# SCH_lora_picobaloon_2023-04-08.net
KiCad netlist of a schematic drawn in EasyEDA
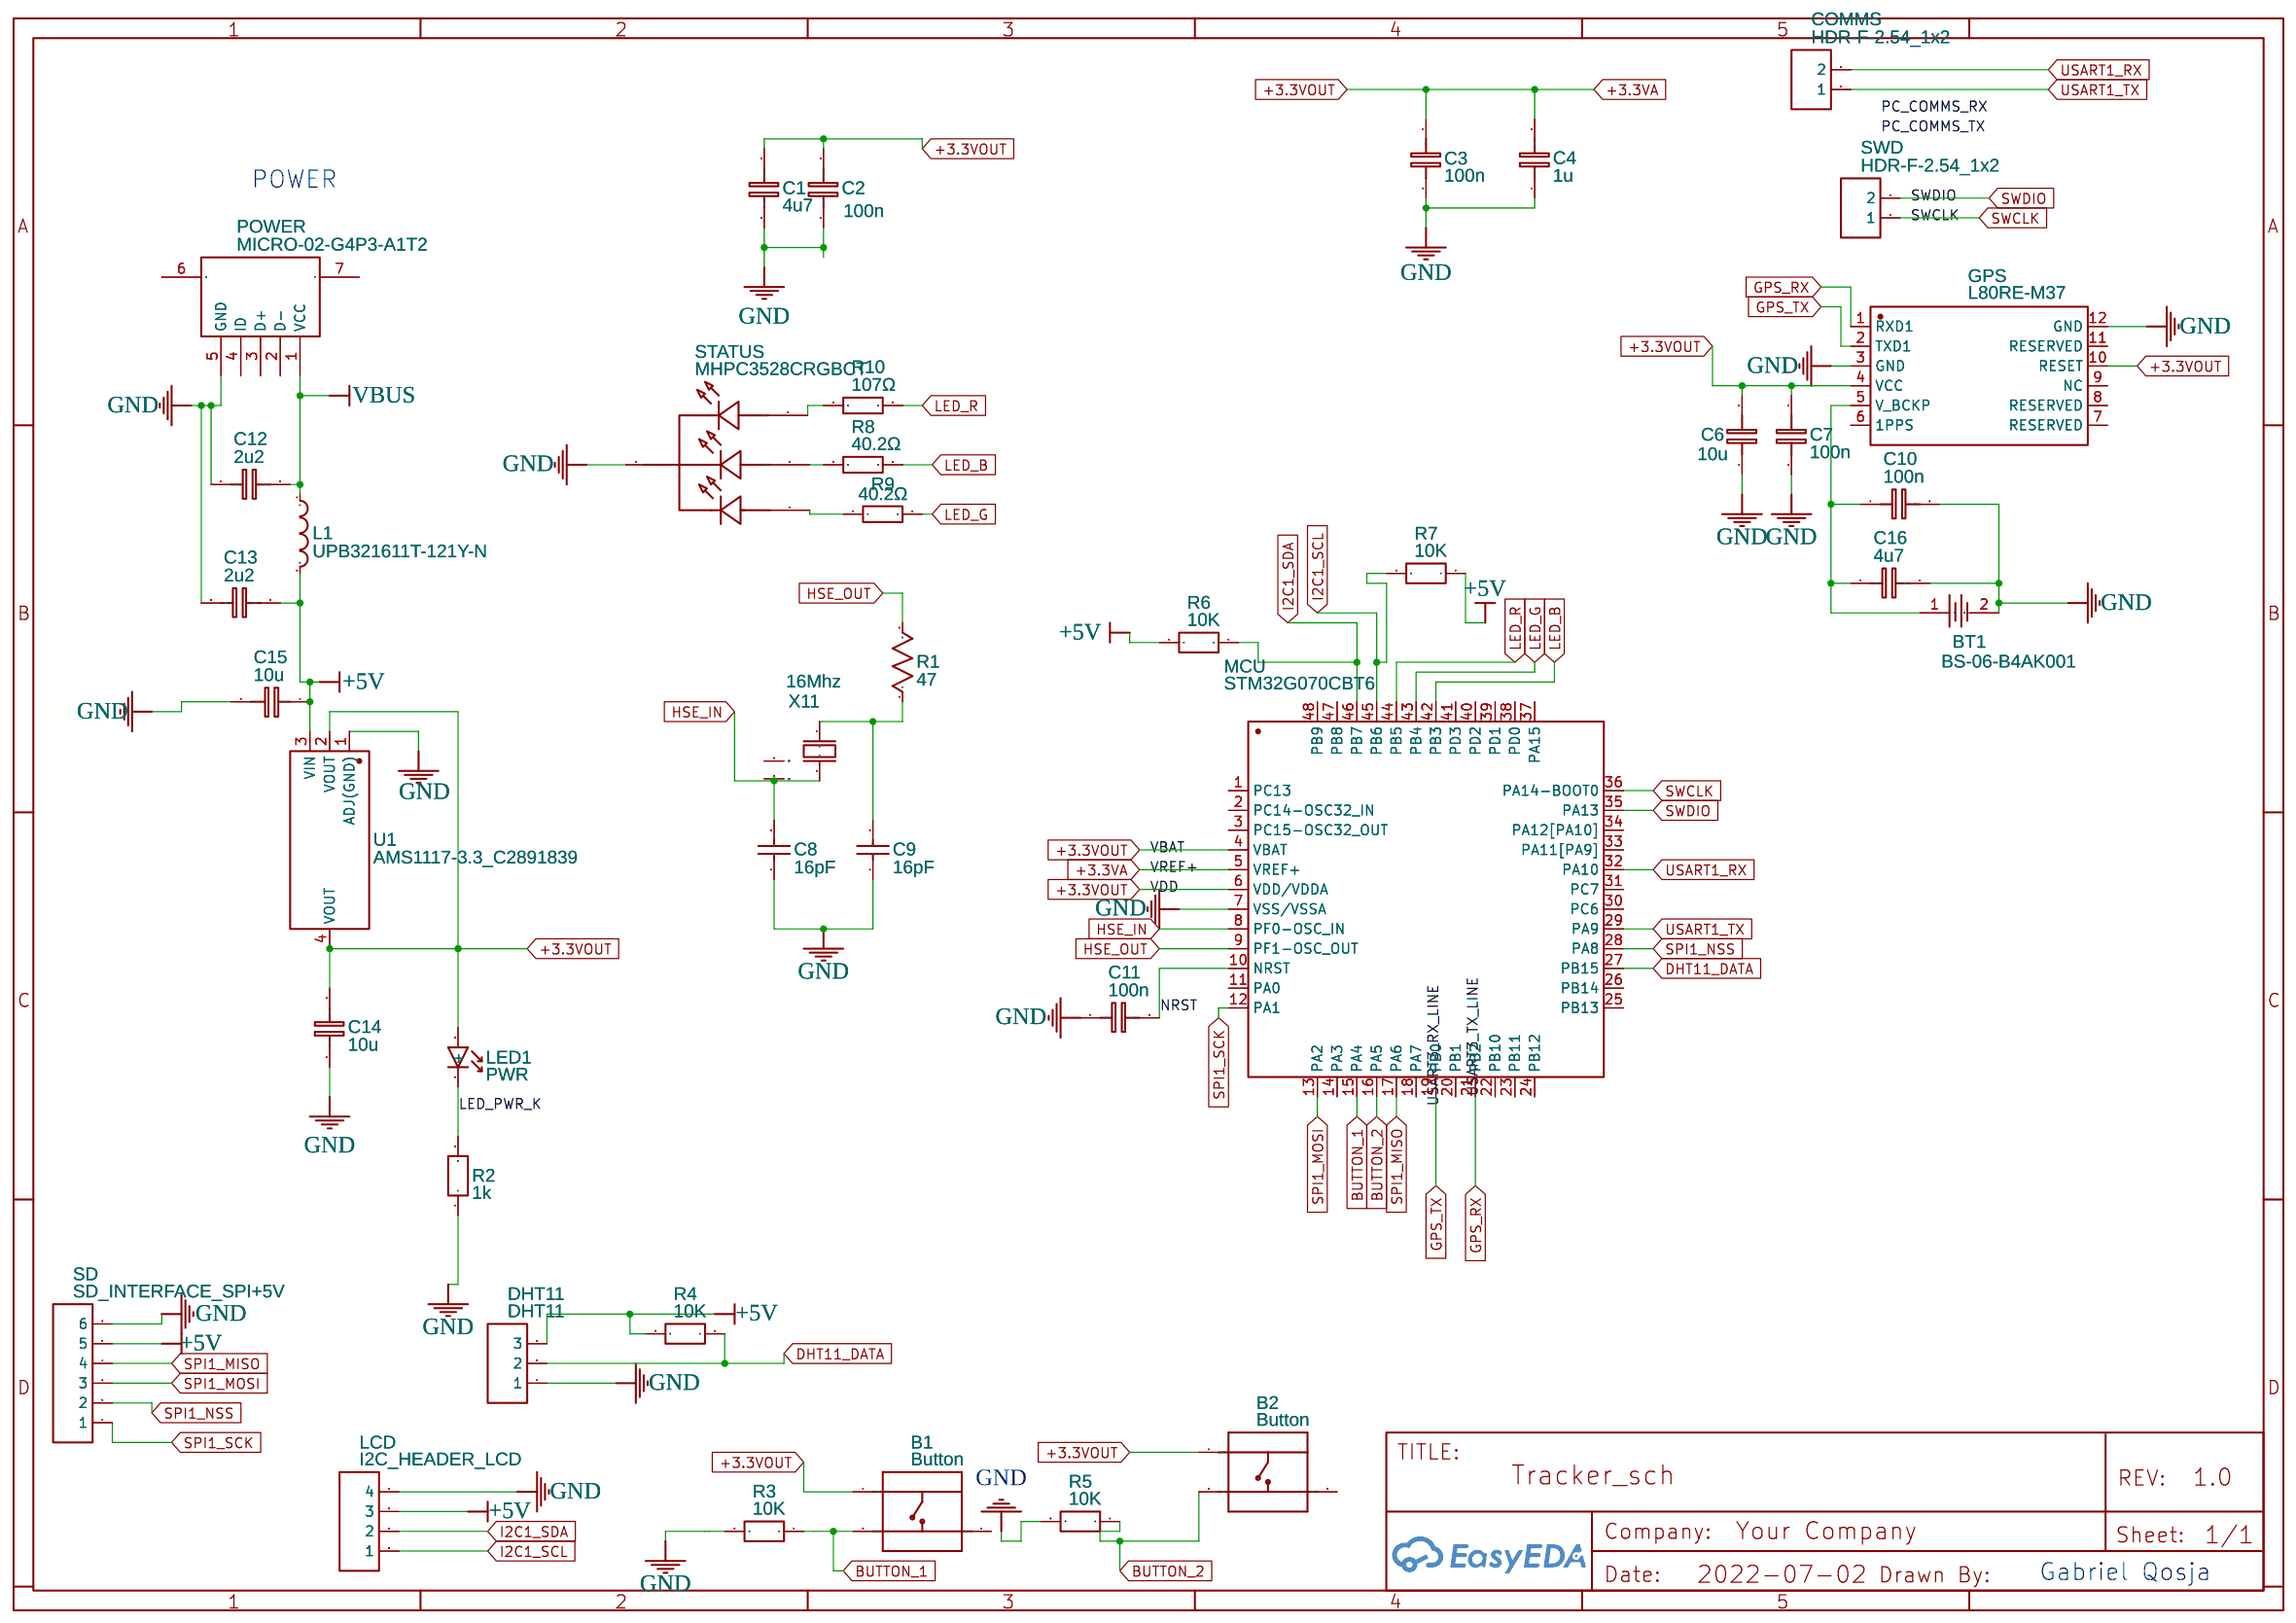
[diagram p0: schematic sheet]

(export (version "E")
  (design (tool "Eeschema 10.0.6"))
  (components
    (comp (ref "B1") (value "Button") (libsource (lib "") (part "Button")))
    (comp (ref "B2") (value "Button") (libsource (lib "") (part "Button")))
    (comp (ref "BT1")
      (value "BS-06-B4AK001")
      (fields (field (name "BOM_Supplier Part") "C964760"))
      (libsource (lib "") (part "BS-06-B4AK001"))
    )
    (comp (ref "C1")
      (value "4u7")
      (fields
        (field (name "BOM_Manufacturer Part") "CL10A475KA8NQNC")
        (field (name "BOM_Supplier Part") "C69335")
      )
      (libsource (lib "") (part "C_0603_EU_5"))
    )
    (comp (ref "C2")
      (value "100n")
      (fields
        (field (name "BOM_Manufacturer Part") "CL10B104KB8NNNC")
        (field (name "BOM_Supplier Part") "C1591")
      )
      (libsource (lib "") (part "C_0603_EU_5"))
    )
    (comp (ref "C3")
      (value "100n")
      (fields
        (field (name "BOM_Manufacturer Part") "CL10B104KB8NNNC")
        (field (name "BOM_Supplier Part") "C1591")
      )
      (libsource (lib "") (part "C_0603_EU_2"))
    )
    (comp (ref "C4")
      (value "1u")
      (fields
        (field (name "BOM_Manufacturer Part") "CL10A105KA8NNNC")
        (field (name "BOM_Supplier Part") "C5673")
      )
      (libsource (lib "") (part "C_0603_EU_2"))
    )
    (comp (ref "C6")
      (value "10u")
      (fields
        (field (name "BOM_Manufacturer Part") "CL10A106MA8NRNC")
        (field (name "BOM_Supplier Part") "C96446")
      )
      (libsource (lib "") (part "C_0603_EU_2"))
    )
    (comp (ref "C7")
      (value "100n")
      (fields
        (field (name "BOM_Manufacturer Part") "CL10B104KB8NNNC")
        (field (name "BOM_Supplier Part") "C1591")
      )
      (libsource (lib "") (part "C_0603_EU_2"))
    )
    (comp (ref "C8")
      (value "16pF")
      (fields
        (field (name "BOM_Manufacturer Part") "CL10C160JB8NNNC")
        (field (name "BOM_Supplier Part") "C170135")
      )
      (libsource (lib "") (part "0603CG160J500NT"))
    )
    (comp (ref "C9")
      (value "16pF")
      (fields
        (field (name "BOM_Manufacturer Part") "CL10C160JB8NNNC")
        (field (name "BOM_Supplier Part") "C170135")
      )
      (libsource (lib "") (part "0603CG160J500NT"))
    )
    (comp (ref "C10")
      (value "100n")
      (fields
        (field (name "BOM_Manufacturer Part") "CL10B104KB8NNNC")
        (field (name "BOM_Supplier Part") "C1591")
      )
      (libsource (lib "") (part "C_0603_EU"))
    )
    (comp (ref "C11")
      (value "100n")
      (fields
        (field (name "BOM_Manufacturer Part") "CL10B104KB8NNNC")
        (field (name "BOM_Supplier Part") "C1591")
      )
      (libsource (lib "") (part "C_0603_EU_1"))
    )
    (comp (ref "C12")
      (value "2u2")
      (fields
        (field (name "BOM_Manufacturer Part") "CL10A225KB8NNNC")
        (field (name "BOM_Supplier Part") "C913904")
      )
      (libsource (lib "") (part "C_0603_EU"))
    )
    (comp (ref "C13")
      (value "2u2")
      (fields
        (field (name "BOM_Manufacturer Part") "CL10A225KB8NNNC")
        (field (name "BOM_Supplier Part") "C913904")
      )
      (libsource (lib "") (part "C_0603_EU_1"))
    )
    (comp (ref "C14")
      (value "10u")
      (fields
        (field (name "BOM_Manufacturer Part") "CL10A106MA8NRNC")
        (field (name "BOM_Supplier Part") "C96446")
      )
      (libsource (lib "") (part "C_0603_EU_3"))
    )
    (comp (ref "C15")
      (value "10u")
      (fields
        (field (name "BOM_Manufacturer Part") "CL10A106MA8NRNC")
        (field (name "BOM_Supplier Part") "C96446")
      )
      (libsource (lib "") (part "C_0603_EU_4"))
    )
    (comp (ref "C16")
      (value "4u7")
      (fields
        (field (name "BOM_Manufacturer Part") "CL10A475KA8NQNC")
        (field (name "BOM_Supplier Part") "C69335")
      )
      (libsource (lib "") (part "C_0603_EU"))
    )
    (comp (ref "COMMS")
      (value "HDR-F-2.54_1x2")
      (fields (field (name "BOM_Supplier Part") "C49661"))
      (libsource (lib "") (part "HDR-F-2.54_1x2_1"))
    )
    (comp (ref "DHT11")
      (value "DHT11")
      (fields (field (name "BOM_Supplier Part") "C146690"))
      (libsource (lib "") (part "HDR-F-2.54_1x3"))
    )
    (comp (ref "GPS")
      (value "L80RE-M37")
      (fields (field (name "BOM_Supplier Part") "C3029061"))
      (libsource (lib "") (part "L80RE-M37"))
    )
    (comp (ref "L1")
      (value "UPB321611T-121Y-N")
      (fields (field (name "BOM_Supplier Part") "C280703"))
      (libsource (lib "") (part "UPB321611T-121Y-N"))
    )
    (comp (ref "LCD")
      (value "I2C_HEADER_LCD")
      (fields (field (name "BOM_Supplier Part") "C225501"))
      (libsource (lib "") (part "HDR-F-2.54_1x4"))
    )
    (comp (ref "LED1") (value "PWR") (libsource (lib "") (part "LED THROUGH HOLE - SIMPLE")))
    (comp (ref "MCU")
      (value "STM32G070CBT6")
      (fields (field (name "BOM_Supplier Part") "C529338"))
      (libsource (lib "") (part "STM32G070CBT6"))
    )
    (comp (ref "POWER")
      (value "MICRO-02-G4P3-A1T2")
      (fields (field (name "BOM_Supplier Part") "C2682527"))
      (libsource (lib "") (part "MICRO-02-G4P3-A1T2"))
    )
    (comp (ref "R1")
      (value "47")
      (fields
        (field (name "BOM_Manufacturer Part") "RT0603BRD0747RL")
        (field (name "BOM_Supplier Part") "C326724")
      )
      (libsource (lib "") (part "R_0603_US"))
    )
    (comp (ref "R2")
      (value "1k")
      (fields
        (field (name "BOM_Manufacturer Part") "AR03FTDX1001")
        (field (name "BOM_Supplier Part") "C304098")
      )
      (libsource (lib "") (part "R_0603_EU_1"))
    )
    (comp (ref "R3")
      (value "10K")
      (fields
        (field (name "BOM_Manufacturer Part") "RT0603BRE0710KL")
        (field (name "BOM_Supplier Part") "C136139")
      )
      (libsource (lib "") (part "R_0603_EU"))
    )
    (comp (ref "R4")
      (value "10K")
      (fields
        (field (name "BOM_Manufacturer Part") "RT0603BRE0710KL")
        (field (name "BOM_Supplier Part") "C136139")
      )
      (libsource (lib "") (part "R_0603_EU"))
    )
    (comp (ref "R5")
      (value "10K")
      (fields
        (field (name "BOM_Manufacturer Part") "RT0603BRE0710KL")
        (field (name "BOM_Supplier Part") "C136139")
      )
      (libsource (lib "") (part "R_0603_EU"))
    )
    (comp (ref "R6")
      (value "10K")
      (fields
        (field (name "BOM_Manufacturer Part") "RT0603BRE0710KL")
        (field (name "BOM_Supplier Part") "C136139")
      )
      (libsource (lib "") (part "R_0603_EU"))
    )
    (comp (ref "R7")
      (value "10K")
      (fields
        (field (name "BOM_Manufacturer Part") "RT0603BRE0710KL")
        (field (name "BOM_Supplier Part") "C136139")
      )
      (libsource (lib "") (part "R_0603_EU"))
    )
    (comp (ref "R8")
      (value "40.2Ω")
      (fields
        (field (name "BOM_Manufacturer Part") "MCR03EZPFX40R2")
        (field (name "BOM_Supplier Part") "C308259")
      )
      (libsource (lib "") (part "MCR03EZPFX40R2"))
    )
    (comp (ref "R9")
      (value "40.2Ω")
      (fields
        (field (name "BOM_Manufacturer Part") "MCR03EZPFX40R2")
        (field (name "BOM_Supplier Part") "C308259")
      )
      (libsource (lib "") (part "MCR03EZPFX40R2"))
    )
    (comp (ref "R10")
      (value "107Ω")
      (fields
        (field (name "BOM_Manufacturer Part") "RS-05K1070FT")
        (field (name "BOM_Supplier Part") "C322239")
      )
      (libsource (lib "") (part "RS-05K1070FT"))
    )
    (comp (ref "SD")
      (value "SD_INTERFACE_SPI+5V")
      (fields (field (name "BOM_Supplier Part") "C40877"))
      (libsource (lib "") (part "HDR-F-2.54_1x6"))
    )
    (comp (ref "STATUS")
      (value "MHPC3528CRGBCT")
      (fields (field (name "BOM_Supplier Part") "C2962096"))
      (libsource (lib "") (part "MHPC3528CRGBCT"))
    )
    (comp (ref "SWD")
      (value "HDR-F-2.54_1x2")
      (fields (field (name "BOM_Supplier Part") "C49661"))
      (libsource (lib "") (part "HDR-F-2.54_1x2"))
    )
    (comp (ref "U1")
      (value "AMS1117-3.3_C2891839")
      (fields
        (field (name "BOM_Manufacturer Part") "AMS1117-3.3")
        (field (name "BOM_Supplier Part") "C2891839")
      )
      (libsource (lib "") (part "AMS1117-3.3_C2891839"))
    )
    (comp (ref "X11")
      (value "16Mhz")
      (fields
        (field (name "BOM_Manufacturer Part") "3225-16.00-12-10-10/A")
        (field (name "BOM_Supplier Part") "C518161")
      )
      (libsource (lib "") (part "XTAL_4-pin_grounded"))
    )
  )
  (nets
    (net (code "1") (name "+3.3VA") (class "Default")
      (node (ref "B1") (pin "1") (pinfunction "A0_1") (pintype "unspecified"))
      (node (ref "B2") (pin "1") (pinfunction "A0_1") (pintype "unspecified"))
      (node (ref "C1") (pin "2") (pinfunction "2_2") (pintype "unspecified"))
      (node (ref "C14") (pin "2") (pinfunction "2_2") (pintype "unspecified"))
      (node (ref "C2") (pin "2") (pinfunction "2_2") (pintype "unspecified"))
      (node (ref "C3") (pin "2") (pinfunction "2_2") (pintype "unspecified"))
      (node (ref "C4") (pin "2") (pinfunction "2_2") (pintype "unspecified"))
      (node (ref "C6") (pin "2") (pinfunction "2_2") (pintype "unspecified"))
      (node (ref "C7") (pin "2") (pinfunction "2_2") (pintype "unspecified"))
      (node (ref "GPS") (pin "10") (pinfunction "RESET_10") (pintype "unspecified"))
      (node (ref "GPS") (pin "4") (pinfunction "VCC_4") (pintype "unspecified"))
      (node (ref "LED1") (pin "1") (pinfunction "+_1") (pintype "unspecified"))
      (node (ref "MCU") (pin "4") (pinfunction "VBAT_4") (pintype "unspecified"))
      (node (ref "MCU") (pin "5") (pinfunction "VREF+_5") (pintype "unspecified"))
      (node (ref "MCU") (pin "6") (pinfunction "VDD/VDDA_6") (pintype "unspecified"))
      (node (ref "U1") (pin "2") (pinfunction "VOUT_2") (pintype "unspecified"))
      (node (ref "U1") (pin "4") (pinfunction "VOUT_4") (pintype "unspecified"))
    )
    (net (code "2") (name "+5V") (class "Default")
      (node (ref "C13") (pin "2") (pinfunction "2_2") (pintype "unspecified"))
      (node (ref "C15") (pin "1") (pinfunction "1_1") (pintype "unspecified"))
      (node (ref "DHT11") (pin "3") (pinfunction "3_3") (pintype "input"))
      (node (ref "L1") (pin "2") (pinfunction "2_2") (pintype "unspecified"))
      (node (ref "LCD") (pin "3") (pinfunction "3_3") (pintype "unspecified"))
      (node (ref "R4") (pin "2") (pinfunction "2_2") (pintype "unspecified"))
      (node (ref "R6") (pin "2") (pinfunction "2_2") (pintype "unspecified"))
      (node (ref "R7") (pin "1") (pinfunction "1_1") (pintype "unspecified"))
      (node (ref "SD") (pin "5") (pinfunction "5_5") (pintype "input"))
      (node (ref "U1") (pin "3") (pinfunction "VIN_3") (pintype "unspecified"))
    )
    (net (code "3") (name "/LED_PWR_K") (class "Default")
      (node (ref "LED1") (pin "2") (pinfunction "-_2") (pintype "unspecified"))
      (node (ref "R2") (pin "2") (pinfunction "2_2") (pintype "unspecified"))
    )
    (net (code "4") (name "/NRST") (class "Default")
      (node (ref "C11") (pin "2") (pinfunction "2_2") (pintype "unspecified"))
      (node (ref "MCU") (pin "10") (pinfunction "NRST_10") (pintype "unspecified"))
    )
    (net (code "7") (name "BUTTON_1") (class "Default")
      (node (ref "B1") (pin "2") (pinfunction "B0_2") (pintype "unspecified"))
      (node (ref "MCU") (pin "15") (pinfunction "PA4_15") (pintype "unspecified"))
      (node (ref "R3") (pin "1") (pinfunction "1_1") (pintype "unspecified"))
    )
    (net (code "8") (name "BUTTON_2") (class "Default")
      (node (ref "B2") (pin "2") (pinfunction "B0_2") (pintype "unspecified"))
      (node (ref "MCU") (pin "16") (pinfunction "PA5_16") (pintype "unspecified"))
      (node (ref "R5") (pin "1") (pinfunction "1_1") (pintype "unspecified"))
    )
    (net (code "9") (name "DHT11_DATA") (class "Default")
      (node (ref "DHT11") (pin "2") (pinfunction "2_2") (pintype "input"))
      (node (ref "MCU") (pin "27") (pinfunction "PB15_27") (pintype "unspecified"))
      (node (ref "R4") (pin "1") (pinfunction "1_1") (pintype "unspecified"))
    )
    (net (code "10") (name "GND") (class "Default")
      (node (ref "BT1") (pin "2") (pinfunction "2_2") (pintype "input"))
      (node (ref "C1") (pin "1") (pinfunction "1_1") (pintype "unspecified"))
      (node (ref "C10") (pin "2") (pinfunction "2_2") (pintype "unspecified"))
      (node (ref "C11") (pin "1") (pinfunction "1_1") (pintype "unspecified"))
      (node (ref "C12") (pin "1") (pinfunction "1_1") (pintype "unspecified"))
      (node (ref "C13") (pin "1") (pinfunction "1_1") (pintype "unspecified"))
      (node (ref "C14") (pin "1") (pinfunction "1_1") (pintype "unspecified"))
      (node (ref "C15") (pin "2") (pinfunction "2_2") (pintype "unspecified"))
      (node (ref "C16") (pin "2") (pinfunction "2_2") (pintype "unspecified"))
      (node (ref "C2") (pin "1") (pinfunction "1_1") (pintype "unspecified"))
      (node (ref "C3") (pin "1") (pinfunction "1_1") (pintype "unspecified"))
      (node (ref "C4") (pin "1") (pinfunction "1_1") (pintype "unspecified"))
      (node (ref "C6") (pin "1") (pinfunction "1_1") (pintype "unspecified"))
      (node (ref "C7") (pin "1") (pinfunction "1_1") (pintype "unspecified"))
      (node (ref "C8") (pin "1") (pinfunction "1_1") (pintype "input"))
      (node (ref "C9") (pin "1") (pinfunction "1_1") (pintype "input"))
      (node (ref "DHT11") (pin "1") (pinfunction "1_1") (pintype "input"))
      (node (ref "GPS") (pin "12") (pinfunction "GND_12") (pintype "unspecified"))
      (node (ref "GPS") (pin "3") (pinfunction "GND_3") (pintype "unspecified"))
      (node (ref "LCD") (pin "4") (pinfunction "4_4") (pintype "unspecified"))
      (node (ref "MCU") (pin "7") (pinfunction "VSS/VSSA_7") (pintype "unspecified"))
      (node (ref "POWER") (pin "5") (pinfunction "GND_5") (pintype "input"))
      (node (ref "R2") (pin "1") (pinfunction "1_1") (pintype "unspecified"))
      (node (ref "R3") (pin "2") (pinfunction "2_2") (pintype "unspecified"))
      (node (ref "R5") (pin "2") (pinfunction "2_2") (pintype "unspecified"))
      (node (ref "SD") (pin "6") (pinfunction "6_6") (pintype "input"))
      (node (ref "STATUS") (pin "4") (pinfunction "-_4") (pintype "unspecified"))
      (node (ref "U1") (pin "1") (pinfunction "ADJ(GND)_1") (pintype "unspecified"))
    )
    (net (code "11") (name "GPS_RX") (class "Default")
      (node (ref "GPS") (pin "1") (pinfunction "RXD1_1") (pintype "unspecified"))
      (node (ref "MCU") (pin "21") (pinfunction "PB2_21") (pintype "unspecified"))
    )
    (net (code "12") (name "GPS_TX") (class "Default")
      (node (ref "GPS") (pin "2") (pinfunction "TXD1_2") (pintype "unspecified"))
      (node (ref "MCU") (pin "19") (pinfunction "PB0_19") (pintype "unspecified"))
    )
    (net (code "13") (name "HSE_IN") (class "Default")
      (node (ref "C8") (pin "2") (pinfunction "2_2") (pintype "input"))
      (node (ref "MCU") (pin "8") (pinfunction "PF0-OSC_IN_8") (pintype "unspecified"))
      (node (ref "X11") (pin "3") (pinfunction "out_3") (pintype "unspecified"))
    )
    (net (code "14") (name "HSE_OUT") (class "Default")
      (node (ref "MCU") (pin "9") (pinfunction "PF1-OSC_OUT_9") (pintype "unspecified"))
      (node (ref "R1") (pin "2") (pinfunction "2_2") (pintype "unspecified"))
    )
    (net (code "15") (name "I2C1_SCL") (class "Default")
      (node (ref "LCD") (pin "1") (pinfunction "1_1") (pintype "unspecified"))
      (node (ref "MCU") (pin "45") (pinfunction "PB6_45") (pintype "unspecified"))
      (node (ref "R7") (pin "2") (pinfunction "2_2") (pintype "unspecified"))
    )
    (net (code "16") (name "I2C1_SDA") (class "Default")
      (node (ref "LCD") (pin "2") (pinfunction "2_2") (pintype "unspecified"))
      (node (ref "MCU") (pin "46") (pinfunction "PB7_46") (pintype "unspecified"))
      (node (ref "R6") (pin "1") (pinfunction "1_1") (pintype "unspecified"))
    )
    (net (code "17") (name "LED_B") (class "Default")
      (node (ref "MCU") (pin "42") (pinfunction "PB3_42") (pintype "unspecified"))
      (node (ref "R8") (pin "2") (pinfunction "2_2") (pintype "unspecified"))
    )
    (net (code "18") (name "LED_G") (class "Default")
      (node (ref "MCU") (pin "43") (pinfunction "PB4_43") (pintype "unspecified"))
      (node (ref "R9") (pin "2") (pinfunction "2_2") (pintype "unspecified"))
    )
    (net (code "19") (name "LED_R") (class "Default")
      (node (ref "MCU") (pin "44") (pinfunction "PB5_44") (pintype "unspecified"))
      (node (ref "R10") (pin "2") (pinfunction "2_2") (pintype "unspecified"))
    )
    (net (code "20") (name "Net-(GPS-V_BCKP)") (class "Default")
      (node (ref "BT1") (pin "1") (pinfunction "1_1") (pintype "input"))
      (node (ref "C10") (pin "1") (pinfunction "1_1") (pintype "unspecified"))
      (node (ref "C16") (pin "1") (pinfunction "1_1") (pintype "unspecified"))
      (node (ref "GPS") (pin "5") (pinfunction "V_BCKP_5") (pintype "unspecified"))
    )
    (net (code "21") (name "Net-(R8-Pad1)") (class "Default")
      (node (ref "R8") (pin "1") (pinfunction "1_1") (pintype "unspecified"))
      (node (ref "STATUS") (pin "2") (pinfunction "+_2") (pintype "unspecified"))
    )
    (net (code "22") (name "Net-(R9-Pad1)") (class "Default")
      (node (ref "R9") (pin "1") (pinfunction "1_1") (pintype "unspecified"))
      (node (ref "STATUS") (pin "3") (pinfunction "+_3") (pintype "unspecified"))
    )
    (net (code "23") (name "Net-(R10-Pad1)") (class "Default")
      (node (ref "R10") (pin "1") (pinfunction "1_1") (pintype "unspecified"))
      (node (ref "STATUS") (pin "1") (pinfunction "+_1") (pintype "unspecified"))
    )
    (net (code "24") (name "Net-(X11-inp)") (class "Default")
      (node (ref "C9") (pin "2") (pinfunction "2_2") (pintype "input"))
      (node (ref "R1") (pin "1") (pinfunction "1_1") (pintype "unspecified"))
      (node (ref "X11") (pin "1") (pinfunction "inp_1") (pintype "unspecified"))
    )
    (net (code "25") (name "SPI1_MISO") (class "Default")
      (node (ref "MCU") (pin "17") (pinfunction "PA6_17") (pintype "unspecified"))
      (node (ref "SD") (pin "4") (pinfunction "4_4") (pintype "input"))
    )
    (net (code "26") (name "SPI1_MOSI") (class "Default")
      (node (ref "MCU") (pin "13") (pinfunction "PA2_13") (pintype "unspecified"))
      (node (ref "SD") (pin "3") (pinfunction "3_3") (pintype "input"))
    )
    (net (code "27") (name "SPI1_NSS") (class "Default")
      (node (ref "MCU") (pin "28") (pinfunction "PA8_28") (pintype "unspecified"))
      (node (ref "SD") (pin "2") (pinfunction "2_2") (pintype "input"))
    )
    (net (code "28") (name "SPI1_SCK") (class "Default")
      (node (ref "MCU") (pin "12") (pinfunction "PA1_12") (pintype "unspecified"))
      (node (ref "SD") (pin "1") (pinfunction "1_1") (pintype "input"))
    )
    (net (code "29") (name "SWCLK") (class "Default")
      (node (ref "MCU") (pin "36") (pinfunction "PA14-BOOT0_36") (pintype "unspecified"))
      (node (ref "SWD") (pin "1") (pinfunction "1_1") (pintype "input"))
    )
    (net (code "30") (name "SWDIO") (class "Default")
      (node (ref "MCU") (pin "35") (pinfunction "PA13_35") (pintype "unspecified"))
      (node (ref "SWD") (pin "2") (pinfunction "2_2") (pintype "input"))
    )
    (net (code "31") (name "USART1_RX") (class "Default")
      (node (ref "COMMS") (pin "2") (pinfunction "2_2") (pintype "input"))
      (node (ref "MCU") (pin "32") (pinfunction "PA10_32") (pintype "unspecified"))
    )
    (net (code "32") (name "USART1_TX") (class "Default")
      (node (ref "COMMS") (pin "1") (pinfunction "1_1") (pintype "input"))
      (node (ref "MCU") (pin "29") (pinfunction "PA9_29") (pintype "unspecified"))
    )
    (net (code "33") (name "VBUS") (class "Default")
      (node (ref "C12") (pin "2") (pinfunction "2_2") (pintype "unspecified"))
      (node (ref "L1") (pin "1") (pinfunction "1_1") (pintype "unspecified"))
      (node (ref "POWER") (pin "1") (pinfunction "VCC_1") (pintype "input"))
    )
    (net (code "34") (name "unconnected-(B1-B1-Pad3)") (class "Default")
      (node (ref "B1") (pin "3") (pinfunction "B1_3") (pintype "unspecified"))
    )
    (net (code "35") (name "unconnected-(B2-B1-Pad3)") (class "Default")
      (node (ref "B2") (pin "3") (pinfunction "B1_3") (pintype "unspecified"))
    )
    (net (code "36") (name "unconnected-(GPS-1PPS-Pad6)") (class "Default")
      (node (ref "GPS") (pin "6") (pinfunction "1PPS_6") (pintype "unspecified"))
    )
    (net (code "37") (name "unconnected-(GPS-NC-Pad9)") (class "Default")
      (node (ref "GPS") (pin "9") (pinfunction "NC_9") (pintype "unspecified"))
    )
    (net (code "38") (name "unconnected-(GPS-RESERVED-Pad7)") (class "Default")
      (node (ref "GPS") (pin "7") (pinfunction "RESERVED_7") (pintype "unspecified"))
    )
    (net (code "39") (name "unconnected-(GPS-RESERVED-Pad8)") (class "Default")
      (node (ref "GPS") (pin "8") (pinfunction "RESERVED_8") (pintype "unspecified"))
    )
    (net (code "40") (name "unconnected-(GPS-RESERVED-Pad11)") (class "Default")
      (node (ref "GPS") (pin "11") (pinfunction "RESERVED_11") (pintype "unspecified"))
    )
    (net (code "41") (name "unconnected-(MCU-PA0-Pad11)") (class "Default")
      (node (ref "MCU") (pin "11") (pinfunction "PA0_11") (pintype "unspecified"))
    )
    (net (code "42") (name "unconnected-(MCU-PA3-Pad14)") (class "Default")
      (node (ref "MCU") (pin "14") (pinfunction "PA3_14") (pintype "unspecified"))
    )
    (net (code "43") (name "unconnected-(MCU-PA7-Pad18)") (class "Default")
      (node (ref "MCU") (pin "18") (pinfunction "PA7_18") (pintype "unspecified"))
    )
    (net (code "44") (name "unconnected-(MCU-PA11[PA9]-Pad33)") (class "Default")
      (node (ref "MCU") (pin "33") (pinfunction "PA11[PA9]_33") (pintype "unspecified"))
    )
    (net (code "45") (name "unconnected-(MCU-PA12[PA10]-Pad34)") (class "Default")
      (node (ref "MCU") (pin "34") (pinfunction "PA12[PA10]_34") (pintype "unspecified"))
    )
    (net (code "46") (name "unconnected-(MCU-PA15-Pad37)") (class "Default")
      (node (ref "MCU") (pin "37") (pinfunction "PA15_37") (pintype "unspecified"))
    )
    (net (code "47") (name "unconnected-(MCU-PB1-Pad20)") (class "Default")
      (node (ref "MCU") (pin "20") (pinfunction "PB1_20") (pintype "unspecified"))
    )
    (net (code "48") (name "unconnected-(MCU-PB8-Pad47)") (class "Default")
      (node (ref "MCU") (pin "47") (pinfunction "PB8_47") (pintype "unspecified"))
    )
    (net (code "49") (name "unconnected-(MCU-PB9-Pad48)") (class "Default")
      (node (ref "MCU") (pin "48") (pinfunction "PB9_48") (pintype "unspecified"))
    )
    (net (code "50") (name "unconnected-(MCU-PB10-Pad22)") (class "Default")
      (node (ref "MCU") (pin "22") (pinfunction "PB10_22") (pintype "unspecified"))
    )
    (net (code "51") (name "unconnected-(MCU-PB11-Pad23)") (class "Default")
      (node (ref "MCU") (pin "23") (pinfunction "PB11_23") (pintype "unspecified"))
    )
    (net (code "52") (name "unconnected-(MCU-PB12-Pad24)") (class "Default")
      (node (ref "MCU") (pin "24") (pinfunction "PB12_24") (pintype "unspecified"))
    )
    (net (code "53") (name "unconnected-(MCU-PB13-Pad25)") (class "Default")
      (node (ref "MCU") (pin "25") (pinfunction "PB13_25") (pintype "unspecified"))
    )
    (net (code "54") (name "unconnected-(MCU-PB14-Pad26)") (class "Default")
      (node (ref "MCU") (pin "26") (pinfunction "PB14_26") (pintype "unspecified"))
    )
    (net (code "55") (name "unconnected-(MCU-PC6-Pad30)") (class "Default")
      (node (ref "MCU") (pin "30") (pinfunction "PC6_30") (pintype "unspecified"))
    )
    (net (code "56") (name "unconnected-(MCU-PC7-Pad31)") (class "Default")
      (node (ref "MCU") (pin "31") (pinfunction "PC7_31") (pintype "unspecified"))
    )
    (net (code "57") (name "unconnected-(MCU-PC13-Pad1)") (class "Default")
      (node (ref "MCU") (pin "1") (pinfunction "PC13_1") (pintype "unspecified"))
    )
    (net (code "58") (name "unconnected-(MCU-PC14-OSC32_IN-Pad2)") (class "Default")
      (node (ref "MCU") (pin "2") (pinfunction "PC14-OSC32_IN_2") (pintype "unspecified"))
    )
    (net (code "59") (name "unconnected-(MCU-PC15-OSC32_OUT-Pad3)") (class "Default")
      (node (ref "MCU") (pin "3") (pinfunction "PC15-OSC32_OUT_3") (pintype "unspecified"))
    )
    (net (code "60") (name "unconnected-(MCU-PD0-Pad38)") (class "Default")
      (node (ref "MCU") (pin "38") (pinfunction "PD0_38") (pintype "unspecified"))
    )
    (net (code "61") (name "unconnected-(MCU-PD1-Pad39)") (class "Default")
      (node (ref "MCU") (pin "39") (pinfunction "PD1_39") (pintype "unspecified"))
    )
    (net (code "62") (name "unconnected-(MCU-PD2-Pad40)") (class "Default")
      (node (ref "MCU") (pin "40") (pinfunction "PD2_40") (pintype "unspecified"))
    )
    (net (code "63") (name "unconnected-(MCU-PD3-Pad41)") (class "Default")
      (node (ref "MCU") (pin "41") (pinfunction "PD3_41") (pintype "unspecified"))
    )
    (net (code "64") (name "unconnected-(POWER-D+-Pad3)") (class "Default")
      (node (ref "POWER") (pin "3") (pinfunction "D+_3") (pintype "input"))
    )
    (net (code "65") (name "unconnected-(POWER-D--Pad2)") (class "Default")
      (node (ref "POWER") (pin "2") (pinfunction "D-_2") (pintype "input"))
    )
    (net (code "66") (name "unconnected-(POWER-ID-Pad4)") (class "Default")
      (node (ref "POWER") (pin "4") (pinfunction "ID_4") (pintype "input"))
    )
    (net (code "67") (name "unconnected-(POWER-Pad6)") (class "Default")
      (node (ref "POWER") (pin "6") (pinfunction "6_6") (pintype "input"))
    )
    (net (code "68") (name "unconnected-(POWER-Pad7)") (class "Default")
      (node (ref "POWER") (pin "7") (pinfunction "7_7") (pintype "input"))
    )
    (net (code "69") (name "unconnected-(X11-GND-Pad2)") (class "Default")
      (node (ref "X11") (pin "2") (pinfunction "GND_2") (pintype "unspecified"))
    )
    (net (code "70") (name "unconnected-(X11-GND-Pad4)") (class "Default")
      (node (ref "X11") (pin "4") (pinfunction "GND_4") (pintype "unspecified"))
    )
  )
)
